# Schemtaic_Sheet_1.net
KiCad netlist of a schematic drawn in Altium Designer
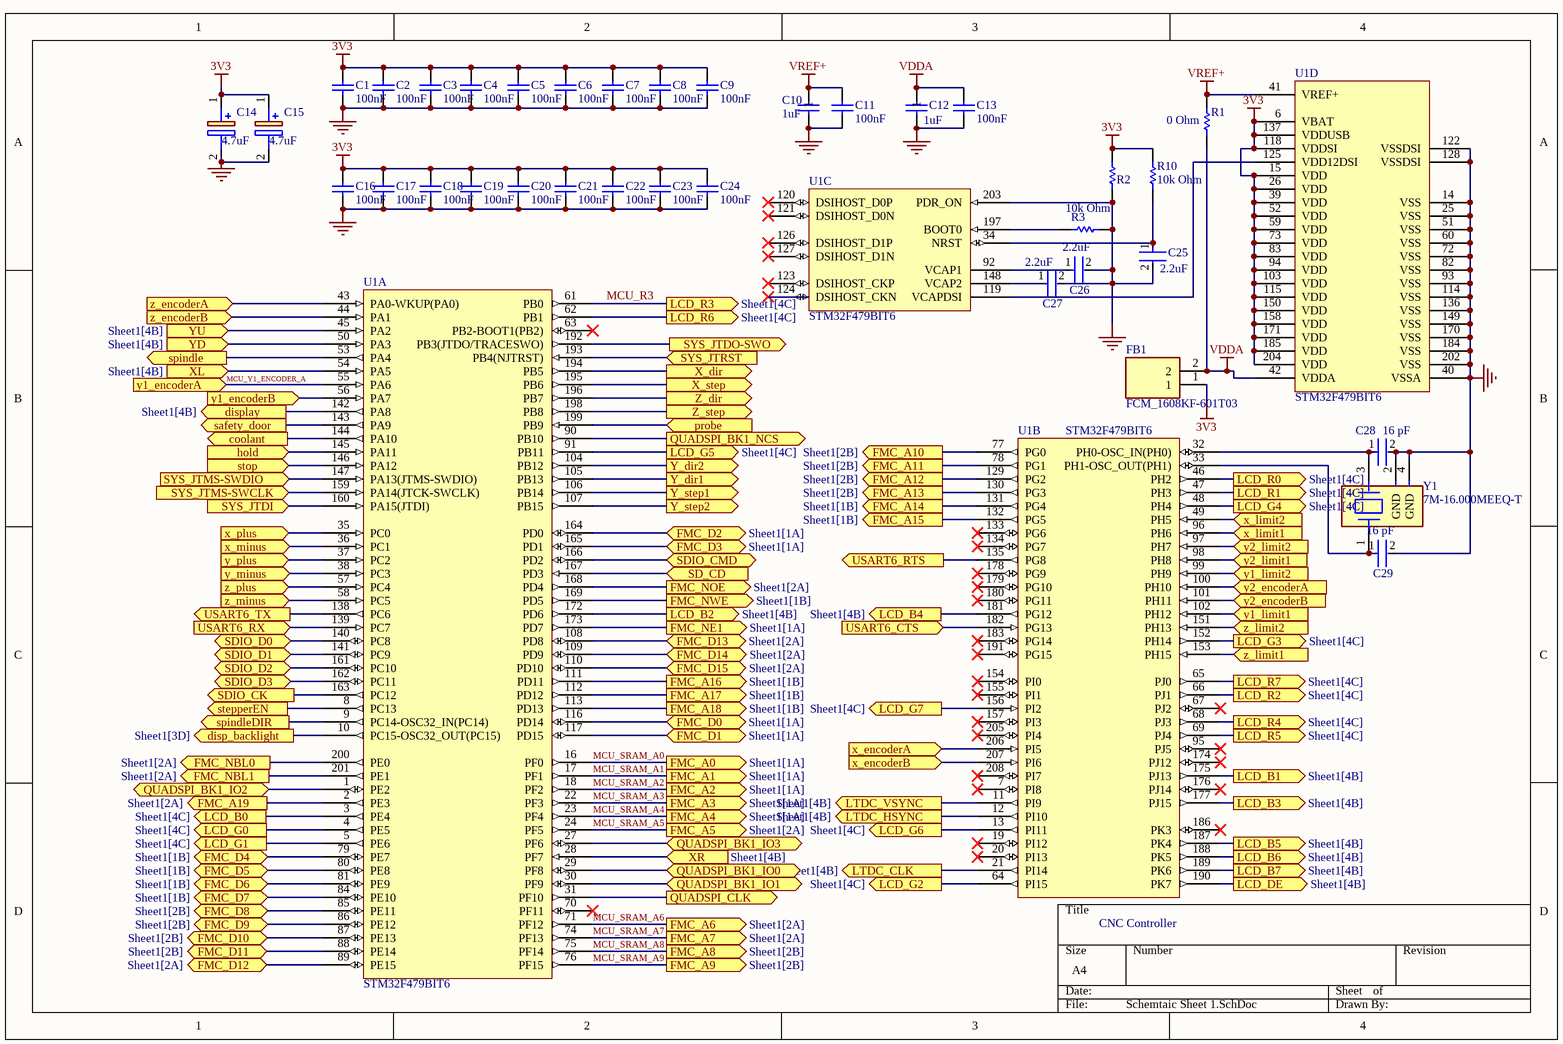
[diagram p0: Schemtaic Sheet 1.SchDoc]

(export (version "E")
  (design (tool "Eeschema 10.0.6"))
  (components
    (comp (ref "C1")
      (value "CL05B104KO5NNNC")
      (footprint "CAPC1050X55X23ML05T13")
      (description "Chip Capacitor, 100 nF, +/- 10%, 16 V, -55 to 125 degC, 0402 (1005 Metric), RoHS, Tape and Reel")
      (fields (field (name "MANUFACTURER") "Samsung Electro-Mechanics") (field (name "CAPACITANCE") "100nF"))
      (libsource (lib "Altium Content Vault") (part "CAP-NP-2"))
    )
    (comp (ref "C2")
      (value "CL05B104KO5NNNC")
      (footprint "CAPC1050X55X23ML05T13")
      (description "Chip Capacitor, 100 nF, +/- 10%, 16 V, -55 to 125 degC, 0402 (1005 Metric), RoHS, Tape and Reel")
      (fields (field (name "MANUFACTURER") "Samsung Electro-Mechanics") (field (name "CAPACITANCE") "100nF"))
      (libsource (lib "Altium Content Vault") (part "CAP-NP-2"))
    )
    (comp (ref "C3")
      (value "CL05B104KO5NNNC")
      (footprint "CAPC1050X55X23ML05T13")
      (description "Chip Capacitor, 100 nF, +/- 10%, 16 V, -55 to 125 degC, 0402 (1005 Metric), RoHS, Tape and Reel")
      (fields (field (name "MANUFACTURER") "Samsung Electro-Mechanics") (field (name "CAPACITANCE") "100nF"))
      (libsource (lib "Altium Content Vault") (part "CAP-NP-2"))
    )
    (comp (ref "C4")
      (value "CL05B104KO5NNNC")
      (footprint "CAPC1050X55X23ML05T13")
      (description "Chip Capacitor, 100 nF, +/- 10%, 16 V, -55 to 125 degC, 0402 (1005 Metric), RoHS, Tape and Reel")
      (fields (field (name "MANUFACTURER") "Samsung Electro-Mechanics") (field (name "CAPACITANCE") "100nF"))
      (libsource (lib "Altium Content Vault") (part "CAP-NP-2"))
    )
    (comp (ref "C5")
      (value "CL05B104KO5NNNC")
      (footprint "CAPC1050X55X23ML05T13")
      (description "Chip Capacitor, 100 nF, +/- 10%, 16 V, -55 to 125 degC, 0402 (1005 Metric), RoHS, Tape and Reel")
      (fields (field (name "MANUFACTURER") "Samsung Electro-Mechanics") (field (name "CAPACITANCE") "100nF"))
      (libsource (lib "Altium Content Vault") (part "CAP-NP-2"))
    )
    (comp (ref "C6")
      (value "CL05B104KO5NNNC")
      (footprint "CAPC1050X55X23ML05T13")
      (description "Chip Capacitor, 100 nF, +/- 10%, 16 V, -55 to 125 degC, 0402 (1005 Metric), RoHS, Tape and Reel")
      (fields (field (name "MANUFACTURER") "Samsung Electro-Mechanics") (field (name "CAPACITANCE") "100nF"))
      (libsource (lib "Altium Content Vault") (part "CAP-NP-2"))
    )
    (comp (ref "C7")
      (value "CL05B104KO5NNNC")
      (footprint "CAPC1050X55X23ML05T13")
      (description "Chip Capacitor, 100 nF, +/- 10%, 16 V, -55 to 125 degC, 0402 (1005 Metric), RoHS, Tape and Reel")
      (fields (field (name "MANUFACTURER") "Samsung Electro-Mechanics") (field (name "CAPACITANCE") "100nF"))
      (libsource (lib "Altium Content Vault") (part "CAP-NP-2"))
    )
    (comp (ref "C8")
      (value "CL05B104KO5NNNC")
      (footprint "CAPC1050X55X23ML05T13")
      (description "Chip Capacitor, 100 nF, +/- 10%, 16 V, -55 to 125 degC, 0402 (1005 Metric), RoHS, Tape and Reel")
      (fields (field (name "MANUFACTURER") "Samsung Electro-Mechanics") (field (name "CAPACITANCE") "100nF"))
      (libsource (lib "Altium Content Vault") (part "CAP-NP-2"))
    )
    (comp (ref "C9")
      (value "CL05B104KO5NNNC")
      (footprint "CAPC1050X55X23ML05T13")
      (description "Chip Capacitor, 100 nF, +/- 10%, 16 V, -55 to 125 degC, 0402 (1005 Metric), RoHS, Tape and Reel")
      (fields (field (name "MANUFACTURER") "Samsung Electro-Mechanics") (field (name "CAPACITANCE") "100nF"))
      (libsource (lib "Altium Content Vault") (part "CAP-NP-2"))
    )
    (comp (ref "C10")
      (value "TACL105K016XTA")
      (footprint "CAPC1609X100X15LL20")
      (fields (field (name "MANUFACTURER") "AVX Interconnect / Elco") (field (name "CAPACITANCE") "1uF"))
      (libsource (lib "Altium Content Vault") (part "CAP"))
    )
    (comp (ref "C11")
      (value "CL05B104KO5NNNC")
      (footprint "CAPC1050X55X23ML05T13")
      (description "Chip Capacitor, 100 nF, +/- 10%, 16 V, -55 to 125 degC, 0402 (1005 Metric), RoHS, Tape and Reel")
      (fields (field (name "MANUFACTURER") "Samsung Electro-Mechanics") (field (name "CAPACITANCE") "100nF"))
      (libsource (lib "Altium Content Vault") (part "CAP-NP-2"))
    )
    (comp (ref "C12")
      (value "TACL105K016XTA")
      (footprint "CAPC1609X100X15LL20")
      (fields (field (name "MANUFACTURER") "AVX Interconnect / Elco") (field (name "CAPACITANCE") "1uF"))
      (libsource (lib "Altium Content Vault") (part "CAP"))
    )
    (comp (ref "C13")
      (value "CL05B104KO5NNNC")
      (footprint "CAPC1050X55X23ML05T13")
      (description "Chip Capacitor, 100 nF, +/- 10%, 16 V, -55 to 125 degC, 0402 (1005 Metric), RoHS, Tape and Reel")
      (fields (field (name "MANUFACTURER") "Samsung Electro-Mechanics") (field (name "CAPACITANCE") "100nF"))
      (libsource (lib "Altium Content Vault") (part "CAP-NP-2"))
    )
    (comp (ref "C14")
      (value "F981C475MMAAJ6")
      (footprint "SamacSys:CAPPM169X100N")
      (description "Capacitor Polarised")
      (fields (field (name "MOUSER PART NUMBER") "581-F981C475MMAAJ6") (field (name "CAPACITANCE") "4.7uF"))
      (libsource (lib "*") (part "F981C475MMAAJ6"))
    )
    (comp (ref "C15")
      (value "F981C475MMAAJ6")
      (footprint "SamacSys:CAPPM169X100N")
      (description "Capacitor Polarised")
      (fields (field (name "MOUSER PART NUMBER") "581-F981C475MMAAJ6") (field (name "CAPACITANCE") "4.7uF"))
      (libsource (lib "*") (part "F981C475MMAAJ6"))
    )
    (comp (ref "C16")
      (value "CL05B104KO5NNNC")
      (footprint "CAPC1050X55X23ML05T13")
      (description "Chip Capacitor, 100 nF, +/- 10%, 16 V, -55 to 125 degC, 0402 (1005 Metric), RoHS, Tape and Reel")
      (fields (field (name "MANUFACTURER") "Samsung Electro-Mechanics") (field (name "CAPACITANCE") "100nF"))
      (libsource (lib "Altium Content Vault") (part "CAP-NP-2"))
    )
    (comp (ref "C17")
      (value "CL05B104KO5NNNC")
      (footprint "CAPC1050X55X23ML05T13")
      (description "Chip Capacitor, 100 nF, +/- 10%, 16 V, -55 to 125 degC, 0402 (1005 Metric), RoHS, Tape and Reel")
      (fields (field (name "MANUFACTURER") "Samsung Electro-Mechanics") (field (name "CAPACITANCE") "100nF"))
      (libsource (lib "Altium Content Vault") (part "CAP-NP-2"))
    )
    (comp (ref "C18")
      (value "CL05B104KO5NNNC")
      (footprint "CAPC1050X55X23ML05T13")
      (description "Chip Capacitor, 100 nF, +/- 10%, 16 V, -55 to 125 degC, 0402 (1005 Metric), RoHS, Tape and Reel")
      (fields (field (name "MANUFACTURER") "Samsung Electro-Mechanics") (field (name "CAPACITANCE") "100nF"))
      (libsource (lib "Altium Content Vault") (part "CAP-NP-2"))
    )
    (comp (ref "C19")
      (value "CL05B104KO5NNNC")
      (footprint "CAPC1050X55X23ML05T13")
      (description "Chip Capacitor, 100 nF, +/- 10%, 16 V, -55 to 125 degC, 0402 (1005 Metric), RoHS, Tape and Reel")
      (fields (field (name "MANUFACTURER") "Samsung Electro-Mechanics") (field (name "CAPACITANCE") "100nF"))
      (libsource (lib "Altium Content Vault") (part "CAP-NP-2"))
    )
    (comp (ref "C20")
      (value "CL05B104KO5NNNC")
      (footprint "CAPC1050X55X23ML05T13")
      (description "Chip Capacitor, 100 nF, +/- 10%, 16 V, -55 to 125 degC, 0402 (1005 Metric), RoHS, Tape and Reel")
      (fields (field (name "MANUFACTURER") "Samsung Electro-Mechanics") (field (name "CAPACITANCE") "100nF"))
      (libsource (lib "Altium Content Vault") (part "CAP-NP-2"))
    )
    (comp (ref "C21")
      (value "CL05B104KO5NNNC")
      (footprint "CAPC1050X55X23ML05T13")
      (description "Chip Capacitor, 100 nF, +/- 10%, 16 V, -55 to 125 degC, 0402 (1005 Metric), RoHS, Tape and Reel")
      (fields (field (name "MANUFACTURER") "Samsung Electro-Mechanics") (field (name "CAPACITANCE") "100nF"))
      (libsource (lib "Altium Content Vault") (part "CAP-NP-2"))
    )
    (comp (ref "C22")
      (value "CL05B104KO5NNNC")
      (footprint "CAPC1050X55X23ML05T13")
      (description "Chip Capacitor, 100 nF, +/- 10%, 16 V, -55 to 125 degC, 0402 (1005 Metric), RoHS, Tape and Reel")
      (fields (field (name "MANUFACTURER") "Samsung Electro-Mechanics") (field (name "CAPACITANCE") "100nF"))
      (libsource (lib "Altium Content Vault") (part "CAP-NP-2"))
    )
    (comp (ref "C23")
      (value "CL05B104KO5NNNC")
      (footprint "CAPC1050X55X23ML05T13")
      (description "Chip Capacitor, 100 nF, +/- 10%, 16 V, -55 to 125 degC, 0402 (1005 Metric), RoHS, Tape and Reel")
      (fields (field (name "MANUFACTURER") "Samsung Electro-Mechanics") (field (name "CAPACITANCE") "100nF"))
      (libsource (lib "Altium Content Vault") (part "CAP-NP-2"))
    )
    (comp (ref "C24")
      (value "CL05B104KO5NNNC")
      (footprint "CAPC1050X55X23ML05T13")
      (description "Chip Capacitor, 100 nF, +/- 10%, 16 V, -55 to 125 degC, 0402 (1005 Metric), RoHS, Tape and Reel")
      (fields (field (name "MANUFACTURER") "Samsung Electro-Mechanics") (field (name "CAPACITANCE") "100nF"))
      (libsource (lib "Altium Content Vault") (part "CAP-NP-2"))
    )
    (comp (ref "C25")
      (value "0603YC225KAT2A")
      (footprint "FP-0603-L_1_6_0_15-W_0_81-IPC_C")
      (description "General Purpose Ceramic Capacitor, 0603, 2.2uF, 10%, X7R, 15%, 16V")
      (fields (field (name "CAPACITANCE") "2.2uF") (field (name "TOLERANCE") "10%"))
      (libsource (lib "Altium Content Vault") (part "02cd4be3c70576c341d710602a673aa"))
    )
    (comp (ref "C26")
      (value "0603YC225KAT2A")
      (footprint "FP-0603-L_1_6_0_15-W_0_81-IPC_C")
      (description "General Purpose Ceramic Capacitor, 0603, 2.2uF, 10%, X7R, 15%, 16V")
      (fields (field (name "CAPACITANCE") "2.2uF") (field (name "TOLERANCE") "10%"))
      (libsource (lib "Altium Content Vault") (part "02cd4be3c70576c341d710602a673aa"))
    )
    (comp (ref "C27")
      (value "0603YC225KAT2A")
      (footprint "FP-0603-L_1_6_0_15-W_0_81-IPC_C")
      (description "General Purpose Ceramic Capacitor, 0603, 2.2uF, 10%, X7R, 15%, 16V")
      (fields (field (name "CAPACITANCE") "2.2uF") (field (name "TOLERANCE") "10%"))
      (libsource (lib "Altium Content Vault") (part "02cd4be3c70576c341d710602a673aa"))
    )
    (comp (ref "C28")
      (value "C0402C160F4HACTU")
      (footprint "FP-C0402-BB-MFG")
      (description "C0402 16 pF X8R 1.00% 16 V")
      (fields
        (field (name "TOLERANCE") "0.01")
        (field (name "CAPACITANCE") "16 pF")
        (field (name "OCTOPART") "https://octopart.com/c0402c160f4hactu-kemet-88724207")
      )
      (libsource (lib "Altium Content Vault") (part "b4654b650e69147ec39a6b967a45e02"))
    )
    (comp (ref "C29")
      (value "16 pF")
      (footprint "FP-C0402-BB-MFG")
      (description "C0402 16 pF X8R 1.00% 16 V")
      (fields (field (name "MANUFACTURER PART NUMBER") "C0402C160F4HACTU") (field (name "TOLERANCE") "0.01"))
      (libsource (lib "Altium Content Vault") (part "b4654b650e69147ec39a6b967a45e02"))
    )
    (comp (ref "FB1")
      (value "FCM_1608KF-601T03")
      (footprint "SamacSys:BEADC1608X95N")
      (description "Ferrite Bead")
      (fields (field (name "MANUFACTURER_PART_NUMBER") "FCM 1608KF-601T03"))
      (libsource (lib "*") (part "FCM_1608KF-601T03"))
    )
    (comp (ref "R1")
      (value "CRCW04020000Z0EDHP")
      (footprint "RESC1005X40X25ML05T10")
      (fields (field (name "MANUFACTURER") "Vishay Dale") (field (name "RESISTANCE") "0 Ohm"))
      (libsource (lib "Altium Content Vault") (part "RES"))
    )
    (comp (ref "R2")
      (value "CRCW040210K0FKEDHP")
      (footprint "RESC1005X40X25ML05T10")
      (fields (field (name "MANUFACTURER") "Vishay Dale"))
      (libsource (lib "Altium Content Vault") (part "RES"))
    )
    (comp (ref "R3")
      (value "CRCW040210K0FKEDHP")
      (footprint "RESC1005X40X25ML05T10")
      (fields (field (name "MANUFACTURER") "Vishay Dale") (field (name "RESISTANCE") "10k Ohm"))
      (libsource (lib "Altium Content Vault") (part "RES"))
    )
    (comp (ref "R10")
      (value "CRCW040210K0FKEDHP")
      (footprint "RESC1005X40X25ML05T10")
      (fields (field (name "MANUFACTURER") "Vishay Dale") (field (name "RESISTANCE") "10k Ohm"))
      (libsource (lib "Altium Content Vault") (part "RES"))
    )
    (comp (ref "U1")
      (value "STM32F479BIT6")
      (footprint "STM-LQFP208_L")
      (libsource (lib "Altium Content Vault") (part "MC-ARM-STM32F479-LQFP208"))
    )
    (comp (ref "Y1")
      (value "7M-16.000MEEQ-T")
      (footprint "FP-7M-MFG")
      (description "Crystal 16MHz, 10ppm, 10pF, 60Ω")
      (fields (field (name "TOLERANCE") "10ppm"))
      (libsource (lib "Altium Content Vault") (part "41079aabb0e87794b56622915be14ed"))
    )
  )
  (nets
    (net (code "1") (name "/FMC_A10") (class "Default")
      (node (ref "U1") (pin "77") (pinfunction "PG0_77") (pintype "bidirectional"))
    )
    (net (code "2") (name "/FMC_A11") (class "Default")
      (node (ref "U1") (pin "78") (pinfunction "PG1_78") (pintype "bidirectional"))
    )
    (net (code "3") (name "/FMC_A12") (class "Default")
      (node (ref "U1") (pin "129") (pinfunction "PG2_129") (pintype "bidirectional"))
    )
    (net (code "4") (name "/FMC_A13") (class "Default")
      (node (ref "U1") (pin "130") (pinfunction "PG3_130") (pintype "bidirectional"))
    )
    (net (code "5") (name "/FMC_A14") (class "Default")
      (node (ref "U1") (pin "131") (pinfunction "PG4_131") (pintype "bidirectional"))
    )
    (net (code "6") (name "/FMC_A15") (class "Default")
      (node (ref "U1") (pin "132") (pinfunction "PG5_132") (pintype "bidirectional"))
    )
    (net (code "7") (name "/FMC_A16") (class "Default")
      (node (ref "U1") (pin "111") (pinfunction "PD11_111") (pintype "bidirectional"))
    )
    (net (code "8") (name "/FMC_A17") (class "Default")
      (node (ref "U1") (pin "112") (pinfunction "PD12_112") (pintype "bidirectional"))
    )
    (net (code "9") (name "/FMC_A18") (class "Default")
      (node (ref "U1") (pin "113") (pinfunction "PD13_113") (pintype "bidirectional"))
    )
    (net (code "10") (name "/FMC_A19") (class "Default")
      (node (ref "U1") (pin "2") (pinfunction "PE3_2") (pintype "bidirectional"))
    )
    (net (code "11") (name "/FMC_D0") (class "Default")
      (node (ref "U1") (pin "116") (pinfunction "PD14_116") (pintype "bidirectional"))
    )
    (net (code "12") (name "/FMC_D1") (class "Default")
      (node (ref "U1") (pin "117") (pinfunction "PD15_117") (pintype "bidirectional"))
    )
    (net (code "13") (name "/FMC_D2") (class "Default")
      (node (ref "U1") (pin "164") (pinfunction "PD0_164") (pintype "bidirectional"))
    )
    (net (code "14") (name "/FMC_D3") (class "Default")
      (node (ref "U1") (pin "165") (pinfunction "PD1_165") (pintype "bidirectional"))
    )
    (net (code "15") (name "/FMC_D4") (class "Default")
      (node (ref "U1") (pin "79") (pinfunction "PE7_79") (pintype "bidirectional"))
    )
    (net (code "16") (name "/FMC_D5") (class "Default")
      (node (ref "U1") (pin "80") (pinfunction "PE8_80") (pintype "bidirectional"))
    )
    (net (code "17") (name "/FMC_D6") (class "Default")
      (node (ref "U1") (pin "81") (pinfunction "PE9_81") (pintype "bidirectional"))
    )
    (net (code "18") (name "/FMC_D7") (class "Default")
      (node (ref "U1") (pin "84") (pinfunction "PE10_84") (pintype "bidirectional"))
    )
    (net (code "19") (name "/FMC_D8") (class "Default")
      (node (ref "U1") (pin "85") (pinfunction "PE11_85") (pintype "bidirectional"))
    )
    (net (code "20") (name "/FMC_D9") (class "Default")
      (node (ref "U1") (pin "86") (pinfunction "PE12_86") (pintype "bidirectional"))
    )
    (net (code "21") (name "/FMC_D10") (class "Default")
      (node (ref "U1") (pin "87") (pinfunction "PE13_87") (pintype "bidirectional"))
    )
    (net (code "22") (name "/FMC_D11") (class "Default")
      (node (ref "U1") (pin "88") (pinfunction "PE14_88") (pintype "bidirectional"))
    )
    (net (code "23") (name "/FMC_D12") (class "Default")
      (node (ref "U1") (pin "89") (pinfunction "PE15_89") (pintype "bidirectional"))
    )
    (net (code "24") (name "/FMC_D13") (class "Default")
      (node (ref "U1") (pin "108") (pinfunction "PD8_108") (pintype "bidirectional"))
    )
    (net (code "25") (name "/FMC_D14") (class "Default")
      (node (ref "U1") (pin "109") (pinfunction "PD9_109") (pintype "bidirectional"))
    )
    (net (code "26") (name "/FMC_D15") (class "Default")
      (node (ref "U1") (pin "110") (pinfunction "PD10_110") (pintype "bidirectional"))
    )
    (net (code "27") (name "/FMC_NBL0") (class "Default")
      (node (ref "U1") (pin "200") (pinfunction "PE0_200") (pintype "bidirectional"))
    )
    (net (code "28") (name "/FMC_NBL1") (class "Default")
      (node (ref "U1") (pin "201") (pinfunction "PE1_201") (pintype "bidirectional"))
    )
    (net (code "29") (name "/FMC_NE1") (class "Default")
      (node (ref "U1") (pin "173") (pinfunction "PD7_173") (pintype "bidirectional"))
    )
    (net (code "30") (name "/FMC_NOE") (class "Default")
      (node (ref "U1") (pin "168") (pinfunction "PD4_168") (pintype "bidirectional"))
    )
    (net (code "31") (name "/FMC_NWE") (class "Default")
      (node (ref "U1") (pin "169") (pinfunction "PD5_169") (pintype "bidirectional"))
    )
    (net (code "32") (name "/LCD_B0") (class "Default")
      (node (ref "U1") (pin "3") (pinfunction "PE4_3") (pintype "bidirectional"))
    )
    (net (code "33") (name "/LCD_B1") (class "Default")
      (node (ref "U1") (pin "175") (pinfunction "PJ13_175") (pintype "bidirectional"))
    )
    (net (code "34") (name "/LCD_B2") (class "Default")
      (node (ref "U1") (pin "172") (pinfunction "PD6_172") (pintype "bidirectional"))
    )
    (net (code "35") (name "/LCD_B3") (class "Default")
      (node (ref "U1") (pin "177") (pinfunction "PJ15_177") (pintype "bidirectional"))
    )
    (net (code "36") (name "/LCD_B4") (class "Default")
      (node (ref "U1") (pin "181") (pinfunction "PG12_181") (pintype "bidirectional"))
    )
    (net (code "37") (name "/LCD_B5") (class "Default")
      (node (ref "U1") (pin "187") (pinfunction "PK4_187") (pintype "bidirectional"))
    )
    (net (code "38") (name "/LCD_B6") (class "Default")
      (node (ref "U1") (pin "188") (pinfunction "PK5_188") (pintype "bidirectional"))
    )
    (net (code "39") (name "/LCD_B7") (class "Default")
      (node (ref "U1") (pin "189") (pinfunction "PK6_189") (pintype "bidirectional"))
    )
    (net (code "40") (name "/LCD_DE") (class "Default")
      (node (ref "U1") (pin "190") (pinfunction "PK7_190") (pintype "bidirectional"))
    )
    (net (code "41") (name "/LCD_G0") (class "Default")
      (node (ref "U1") (pin "4") (pinfunction "PE5_4") (pintype "bidirectional"))
    )
    (net (code "42") (name "/LCD_G1") (class "Default")
      (node (ref "U1") (pin "5") (pinfunction "PE6_5") (pintype "bidirectional"))
    )
    (net (code "43") (name "/LCD_G2") (class "Default")
      (node (ref "U1") (pin "64") (pinfunction "PI15_64") (pintype "bidirectional"))
    )
    (net (code "44") (name "/LCD_G3") (class "Default")
      (node (ref "U1") (pin "152") (pinfunction "PH14_152") (pintype "bidirectional"))
    )
    (net (code "45") (name "/LCD_G4") (class "Default")
      (node (ref "U1") (pin "48") (pinfunction "PH4_48") (pintype "bidirectional"))
    )
    (net (code "46") (name "/LCD_G5") (class "Default")
      (node (ref "U1") (pin "91") (pinfunction "PB11_91") (pintype "bidirectional"))
    )
    (net (code "47") (name "/LCD_G6") (class "Default")
      (node (ref "U1") (pin "13") (pinfunction "PI11_13") (pintype "bidirectional"))
    )
    (net (code "48") (name "/LCD_G7") (class "Default")
      (node (ref "U1") (pin "156") (pinfunction "PI2_156") (pintype "bidirectional"))
    )
    (net (code "49") (name "/LCD_R0") (class "Default")
      (node (ref "U1") (pin "46") (pinfunction "PH2_46") (pintype "bidirectional"))
    )
    (net (code "50") (name "/LCD_R1") (class "Default")
      (node (ref "U1") (pin "47") (pinfunction "PH3_47") (pintype "bidirectional"))
    )
    (net (code "51") (name "/LCD_R2") (class "Default")
      (node (ref "U1") (pin "66") (pinfunction "PJ1_66") (pintype "bidirectional"))
    )
    (net (code "52") (name "/LCD_R4") (class "Default")
      (node (ref "U1") (pin "68") (pinfunction "PJ3_68") (pintype "bidirectional"))
    )
    (net (code "53") (name "/LCD_R5") (class "Default")
      (node (ref "U1") (pin "69") (pinfunction "PJ4_69") (pintype "bidirectional"))
    )
    (net (code "54") (name "/LCD_R6") (class "Default")
      (node (ref "U1") (pin "62") (pinfunction "PB1_62") (pintype "bidirectional"))
    )
    (net (code "55") (name "/LCD_R7") (class "Default")
      (node (ref "U1") (pin "65") (pinfunction "PJ0_65") (pintype "bidirectional"))
    )
    (net (code "56") (name "/LTDC_CLK") (class "Default")
      (node (ref "U1") (pin "21") (pinfunction "PI14_21") (pintype "bidirectional"))
    )
    (net (code "57") (name "/LTDC_HSYNC") (class "Default")
      (node (ref "U1") (pin "12") (pinfunction "PI10_12") (pintype "bidirectional"))
    )
    (net (code "58") (name "/LTDC_VSYNC") (class "Default")
      (node (ref "U1") (pin "11") (pinfunction "PI9_11") (pintype "bidirectional"))
    )
    (net (code "59") (name "/MCU_R3") (class "Default")
      (node (ref "U1") (pin "61") (pinfunction "PB0_61") (pintype "bidirectional"))
    )
    (net (code "60") (name "/MCU_SRAM_A0") (class "Default")
      (node (ref "U1") (pin "16") (pinfunction "PF0_16") (pintype "bidirectional"))
    )
    (net (code "61") (name "/MCU_SRAM_A1") (class "Default")
      (node (ref "U1") (pin "17") (pinfunction "PF1_17") (pintype "bidirectional"))
    )
    (net (code "62") (name "/MCU_SRAM_A2") (class "Default")
      (node (ref "U1") (pin "18") (pinfunction "PF2_18") (pintype "bidirectional"))
    )
    (net (code "63") (name "/MCU_SRAM_A3") (class "Default")
      (node (ref "U1") (pin "22") (pinfunction "PF3_22") (pintype "bidirectional"))
    )
    (net (code "64") (name "/MCU_SRAM_A4") (class "Default")
      (node (ref "U1") (pin "23") (pinfunction "PF4_23") (pintype "bidirectional"))
    )
    (net (code "65") (name "/MCU_SRAM_A5") (class "Default")
      (node (ref "U1") (pin "24") (pinfunction "PF5_24") (pintype "bidirectional"))
    )
    (net (code "66") (name "/MCU_SRAM_A6") (class "Default")
      (node (ref "U1") (pin "71") (pinfunction "PF12_71") (pintype "bidirectional"))
    )
    (net (code "67") (name "/MCU_SRAM_A7") (class "Default")
      (node (ref "U1") (pin "74") (pinfunction "PF13_74") (pintype "bidirectional"))
    )
    (net (code "68") (name "/MCU_SRAM_A8") (class "Default")
      (node (ref "U1") (pin "75") (pinfunction "PF14_75") (pintype "bidirectional"))
    )
    (net (code "69") (name "/MCU_SRAM_A9") (class "Default")
      (node (ref "U1") (pin "76") (pinfunction "PF15_76") (pintype "bidirectional"))
    )
    (net (code "70") (name "/MCU_Y1_ENCODER_A") (class "Default")
      (node (ref "U1") (pin "55") (pinfunction "PA6_55") (pintype "bidirectional"))
    )
    (net (code "71") (name "/QUADSPI_BK1_IO0") (class "Default")
      (node (ref "U1") (pin "29") (pinfunction "PF8_29") (pintype "bidirectional"))
    )
    (net (code "72") (name "/QUADSPI_BK1_IO1") (class "Default")
      (node (ref "U1") (pin "30") (pinfunction "PF9_30") (pintype "bidirectional"))
    )
    (net (code "73") (name "/QUADSPI_BK1_IO2") (class "Default")
      (node (ref "U1") (pin "1") (pinfunction "PE2_1") (pintype "bidirectional"))
    )
    (net (code "74") (name "/QUADSPI_BK1_IO3") (class "Default")
      (node (ref "U1") (pin "27") (pinfunction "PF6_27") (pintype "bidirectional"))
    )
    (net (code "75") (name "/QUADSPI_BK1_NCS") (class "Default")
      (node (ref "U1") (pin "90") (pinfunction "PB10_90") (pintype "bidirectional"))
    )
    (net (code "76") (name "/QUADSPI_CLK") (class "Default")
      (node (ref "U1") (pin "31") (pinfunction "PF10_31") (pintype "bidirectional"))
    )
    (net (code "77") (name "/SDIO_CK") (class "Default")
      (node (ref "U1") (pin "163") (pinfunction "PC12_163") (pintype "bidirectional"))
    )
    (net (code "78") (name "/SDIO_CMD") (class "Default")
      (node (ref "U1") (pin "166") (pinfunction "PD2_166") (pintype "bidirectional"))
    )
    (net (code "79") (name "/SDIO_D0") (class "Default")
      (node (ref "U1") (pin "140") (pinfunction "PC8_140") (pintype "bidirectional"))
    )
    (net (code "80") (name "/SDIO_D1") (class "Default")
      (node (ref "U1") (pin "141") (pinfunction "PC9_141") (pintype "bidirectional"))
    )
    (net (code "81") (name "/SDIO_D2") (class "Default")
      (node (ref "U1") (pin "161") (pinfunction "PC10_161") (pintype "bidirectional"))
    )
    (net (code "82") (name "/SDIO_D3") (class "Default")
      (node (ref "U1") (pin "162") (pinfunction "PC11_162") (pintype "bidirectional"))
    )
    (net (code "83") (name "/SD_CD") (class "Default")
      (node (ref "U1") (pin "167") (pinfunction "PD3_167") (pintype "bidirectional"))
    )
    (net (code "84") (name "/SYS_JTDI") (class "Default")
      (node (ref "U1") (pin "160") (pinfunction "PA15(JTDI)_160") (pintype "bidirectional"))
    )
    (net (code "85") (name "/SYS_JTDO-SWO") (class "Default")
      (node (ref "U1") (pin "192") (pinfunction "PB3(JTDO/TRACESWO)_192") (pintype "bidirectional"))
    )
    (net (code "86") (name "/SYS_JTMS-SWCLK") (class "Default")
      (node (ref "U1") (pin "159") (pinfunction "PA14(JTCK-SWCLK)_159") (pintype "bidirectional"))
    )
    (net (code "87") (name "/SYS_JTMS-SWDIO") (class "Default")
      (node (ref "U1") (pin "147") (pinfunction "PA13(JTMS-SWDIO)_147") (pintype "bidirectional"))
    )
    (net (code "88") (name "/SYS_JTRST") (class "Default")
      (node (ref "U1") (pin "193") (pinfunction "PB4(NJTRST)_193") (pintype "bidirectional"))
    )
    (net (code "89") (name "/USART6_CTS") (class "Default")
      (node (ref "U1") (pin "182") (pinfunction "PG13_182") (pintype "bidirectional"))
    )
    (net (code "90") (name "/USART6_RTS") (class "Default")
      (node (ref "U1") (pin "135") (pinfunction "PG8_135") (pintype "bidirectional"))
    )
    (net (code "91") (name "/USART6_RX") (class "Default")
      (node (ref "U1") (pin "139") (pinfunction "PC7_139") (pintype "bidirectional"))
    )
    (net (code "92") (name "/USART6_TX") (class "Default")
      (node (ref "U1") (pin "138") (pinfunction "PC6_138") (pintype "bidirectional"))
    )
    (net (code "93") (name "/XL") (class "Default")
      (node (ref "U1") (pin "54") (pinfunction "PA5_54") (pintype "bidirectional"))
    )
    (net (code "94") (name "/XR") (class "Default")
      (node (ref "U1") (pin "28") (pinfunction "PF7_28") (pintype "bidirectional"))
    )
    (net (code "95") (name "/X_dir") (class "Default")
      (node (ref "U1") (pin "194") (pinfunction "PB5_194") (pintype "bidirectional"))
    )
    (net (code "96") (name "/X_step") (class "Default")
      (node (ref "U1") (pin "195") (pinfunction "PB6_195") (pintype "bidirectional"))
    )
    (net (code "97") (name "/YD") (class "Default")
      (node (ref "U1") (pin "50") (pinfunction "PA3_50") (pintype "bidirectional"))
    )
    (net (code "98") (name "/YU") (class "Default")
      (node (ref "U1") (pin "45") (pinfunction "PA2_45") (pintype "bidirectional"))
    )
    (net (code "99") (name "/Y_dir1") (class "Default")
      (node (ref "U1") (pin "105") (pinfunction "PB13_105") (pintype "bidirectional"))
    )
    (net (code "100") (name "/Y_dir2") (class "Default")
      (node (ref "U1") (pin "104") (pinfunction "PB12_104") (pintype "bidirectional"))
    )
    (net (code "101") (name "/Y_step1") (class "Default")
      (node (ref "U1") (pin "106") (pinfunction "PB14_106") (pintype "bidirectional"))
    )
    (net (code "102") (name "/Y_step2") (class "Default")
      (node (ref "U1") (pin "107") (pinfunction "PB15_107") (pintype "bidirectional"))
    )
    (net (code "103") (name "/Z_dir") (class "Default")
      (node (ref "U1") (pin "196") (pinfunction "PB7_196") (pintype "bidirectional"))
    )
    (net (code "104") (name "/Z_step") (class "Default")
      (node (ref "U1") (pin "198") (pinfunction "PB8_198") (pintype "bidirectional"))
    )
    (net (code "105") (name "/coolant") (class "Default")
      (node (ref "U1") (pin "144") (pinfunction "PA10_144") (pintype "bidirectional"))
    )
    (net (code "106") (name "/disp_backlight") (class "Default")
      (node (ref "U1") (pin "10") (pinfunction "PC15-OSC32_OUT(PC15)_10") (pintype "bidirectional"))
    )
    (net (code "107") (name "/display") (class "Default")
      (node (ref "U1") (pin "142") (pinfunction "PA8_142") (pintype "bidirectional"))
    )
    (net (code "108") (name "/hold") (class "Default")
      (node (ref "U1") (pin "145") (pinfunction "PA11_145") (pintype "bidirectional"))
    )
    (net (code "109") (name "/probe") (class "Default")
      (node (ref "U1") (pin "199") (pinfunction "PB9_199") (pintype "bidirectional"))
    )
    (net (code "110") (name "/safety_door") (class "Default")
      (node (ref "U1") (pin "143") (pinfunction "PA9_143") (pintype "bidirectional"))
    )
    (net (code "111") (name "/spindle") (class "Default")
      (node (ref "U1") (pin "53") (pinfunction "PA4_53") (pintype "bidirectional"))
    )
    (net (code "112") (name "/spindleDIR") (class "Default")
      (node (ref "U1") (pin "9") (pinfunction "PC14-OSC32_IN(PC14)_9") (pintype "bidirectional"))
    )
    (net (code "113") (name "/stepperEN") (class "Default")
      (node (ref "U1") (pin "8") (pinfunction "PC13_8") (pintype "bidirectional"))
    )
    (net (code "114") (name "/stop") (class "Default")
      (node (ref "U1") (pin "146") (pinfunction "PA12_146") (pintype "bidirectional"))
    )
    (net (code "115") (name "/x_encoderA") (class "Default")
      (node (ref "U1") (pin "206") (pinfunction "PI5_206") (pintype "bidirectional"))
    )
    (net (code "116") (name "/x_encoderB") (class "Default")
      (node (ref "U1") (pin "207") (pinfunction "PI6_207") (pintype "bidirectional"))
    )
    (net (code "117") (name "/x_limit1") (class "Default")
      (node (ref "U1") (pin "96") (pinfunction "PH6_96") (pintype "bidirectional"))
    )
    (net (code "118") (name "/x_limit2") (class "Default")
      (node (ref "U1") (pin "49") (pinfunction "PH5_49") (pintype "bidirectional"))
    )
    (net (code "119") (name "/x_minus") (class "Default")
      (node (ref "U1") (pin "36") (pinfunction "PC1_36") (pintype "bidirectional"))
    )
    (net (code "120") (name "/x_plus") (class "Default")
      (node (ref "U1") (pin "35") (pinfunction "PC0_35") (pintype "bidirectional"))
    )
    (net (code "121") (name "/y1_encoderB") (class "Default")
      (node (ref "U1") (pin "56") (pinfunction "PA7_56") (pintype "bidirectional"))
    )
    (net (code "122") (name "/y1_limit1") (class "Default")
      (node (ref "U1") (pin "102") (pinfunction "PH12_102") (pintype "bidirectional"))
    )
    (net (code "123") (name "/y1_limit2") (class "Default")
      (node (ref "U1") (pin "99") (pinfunction "PH9_99") (pintype "bidirectional"))
    )
    (net (code "124") (name "/y2_encoderA") (class "Default")
      (node (ref "U1") (pin "100") (pinfunction "PH10_100") (pintype "bidirectional"))
    )
    (net (code "125") (name "/y2_encoderB") (class "Default")
      (node (ref "U1") (pin "101") (pinfunction "PH11_101") (pintype "bidirectional"))
    )
    (net (code "126") (name "/y2_limit1") (class "Default")
      (node (ref "U1") (pin "98") (pinfunction "PH8_98") (pintype "bidirectional"))
    )
    (net (code "127") (name "/y2_limit2") (class "Default")
      (node (ref "U1") (pin "97") (pinfunction "PH7_97") (pintype "bidirectional"))
    )
    (net (code "128") (name "/y_minus") (class "Default")
      (node (ref "U1") (pin "38") (pinfunction "PC3_38") (pintype "bidirectional"))
    )
    (net (code "129") (name "/y_plus") (class "Default")
      (node (ref "U1") (pin "37") (pinfunction "PC2_37") (pintype "bidirectional"))
    )
    (net (code "130") (name "/z_encoderA") (class "Default")
      (node (ref "U1") (pin "43") (pinfunction "PA0-WKUP(PA0)_43") (pintype "bidirectional"))
    )
    (net (code "131") (name "/z_encoderB") (class "Default")
      (node (ref "U1") (pin "44") (pinfunction "PA1_44") (pintype "bidirectional"))
    )
    (net (code "132") (name "/z_limit1") (class "Default")
      (node (ref "U1") (pin "153") (pinfunction "PH15_153") (pintype "bidirectional"))
    )
    (net (code "133") (name "/z_limit2") (class "Default")
      (node (ref "U1") (pin "151") (pinfunction "PH13_151") (pintype "bidirectional"))
    )
    (net (code "134") (name "/z_minus") (class "Default")
      (node (ref "U1") (pin "58") (pinfunction "PC5_58") (pintype "bidirectional"))
    )
    (net (code "135") (name "/z_plus") (class "Default")
      (node (ref "U1") (pin "57") (pinfunction "PC4_57") (pintype "bidirectional"))
    )
    (net (code "136") (name "3V3") (class "Default")
      (node (ref "C1") (pin "2") (pinfunction "2_2") (pintype "passive"))
      (node (ref "C14") (pin "1") (pinfunction "+_1") (pintype "passive"))
      (node (ref "C15") (pin "1") (pinfunction "+_1") (pintype "passive"))
      (node (ref "C16") (pin "2") (pinfunction "2_2") (pintype "passive"))
      (node (ref "C17") (pin "2") (pinfunction "2_2") (pintype "passive"))
      (node (ref "C18") (pin "2") (pinfunction "2_2") (pintype "passive"))
      (node (ref "C19") (pin "2") (pinfunction "2_2") (pintype "passive"))
      (node (ref "C2") (pin "2") (pinfunction "2_2") (pintype "passive"))
      (node (ref "C20") (pin "2") (pinfunction "2_2") (pintype "passive"))
      (node (ref "C21") (pin "2") (pinfunction "2_2") (pintype "passive"))
      (node (ref "C22") (pin "2") (pinfunction "2_2") (pintype "passive"))
      (node (ref "C23") (pin "2") (pinfunction "2_2") (pintype "passive"))
      (node (ref "C24") (pin "2") (pinfunction "2_2") (pintype "passive"))
      (node (ref "C3") (pin "2") (pinfunction "2_2") (pintype "passive"))
      (node (ref "C4") (pin "2") (pinfunction "2_2") (pintype "passive"))
      (node (ref "C5") (pin "2") (pinfunction "2_2") (pintype "passive"))
      (node (ref "C6") (pin "2") (pinfunction "2_2") (pintype "passive"))
      (node (ref "C7") (pin "2") (pinfunction "2_2") (pintype "passive"))
      (node (ref "C8") (pin "2") (pinfunction "2_2") (pintype "passive"))
      (node (ref "C9") (pin "2") (pinfunction "2_2") (pintype "passive"))
      (node (ref "FB1") (pin "1") (pinfunction "1_1") (pintype "passive"))
      (node (ref "R10") (pin "2") (pinfunction "2_2") (pintype "passive"))
      (node (ref "R2") (pin "2") (pinfunction "2_2") (pintype "passive"))
      (node (ref "U1") (pin "103") (pinfunction "VDD_103") (pintype "power_in"))
      (node (ref "U1") (pin "115") (pinfunction "VDD_115") (pintype "power_in"))
      (node (ref "U1") (pin "118") (pinfunction "VDDSI_118") (pintype "power_in"))
      (node (ref "U1") (pin "137") (pinfunction "VDDUSB_137") (pintype "power_in"))
      (node (ref "U1") (pin "15") (pinfunction "VDD_15") (pintype "power_in"))
      (node (ref "U1") (pin "150") (pinfunction "VDD_150") (pintype "power_in"))
      (node (ref "U1") (pin "158") (pinfunction "VDD_158") (pintype "power_in"))
      (node (ref "U1") (pin "171") (pinfunction "VDD_171") (pintype "power_in"))
      (node (ref "U1") (pin "185") (pinfunction "VDD_185") (pintype "power_in"))
      (node (ref "U1") (pin "204") (pinfunction "VDD_204") (pintype "power_in"))
      (node (ref "U1") (pin "26") (pinfunction "VDD_26") (pintype "power_in"))
      (node (ref "U1") (pin "39") (pinfunction "VDD_39") (pintype "power_in"))
      (node (ref "U1") (pin "52") (pinfunction "VDD_52") (pintype "power_in"))
      (node (ref "U1") (pin "59") (pinfunction "VDD_59") (pintype "power_in"))
      (node (ref "U1") (pin "6") (pinfunction "VBAT_6") (pintype "power_in"))
      (node (ref "U1") (pin "73") (pinfunction "VDD_73") (pintype "power_in"))
      (node (ref "U1") (pin "83") (pinfunction "VDD_83") (pintype "power_in"))
      (node (ref "U1") (pin "94") (pinfunction "VDD_94") (pintype "power_in"))
    )
    (net (code "137") (name "GND") (class "Default")
      (node (ref "C1") (pin "1") (pinfunction "1_1") (pintype "passive"))
      (node (ref "C10") (pin "1") (pinfunction "1_1") (pintype "passive"))
      (node (ref "C11") (pin "1") (pinfunction "1_1") (pintype "passive"))
      (node (ref "C12") (pin "1") (pinfunction "1_1") (pintype "passive"))
      (node (ref "C13") (pin "1") (pinfunction "1_1") (pintype "passive"))
      (node (ref "C14") (pin "2") (pinfunction "-_2") (pintype "passive"))
      (node (ref "C15") (pin "2") (pinfunction "-_2") (pintype "passive"))
      (node (ref "C16") (pin "1") (pinfunction "1_1") (pintype "passive"))
      (node (ref "C17") (pin "1") (pinfunction "1_1") (pintype "passive"))
      (node (ref "C18") (pin "1") (pinfunction "1_1") (pintype "passive"))
      (node (ref "C19") (pin "1") (pinfunction "1_1") (pintype "passive"))
      (node (ref "C2") (pin "1") (pinfunction "1_1") (pintype "passive"))
      (node (ref "C20") (pin "1") (pinfunction "1_1") (pintype "passive"))
      (node (ref "C21") (pin "1") (pinfunction "1_1") (pintype "passive"))
      (node (ref "C22") (pin "1") (pinfunction "1_1") (pintype "passive"))
      (node (ref "C23") (pin "1") (pinfunction "1_1") (pintype "passive"))
      (node (ref "C24") (pin "1") (pinfunction "1_1") (pintype "passive"))
      (node (ref "C25") (pin "2") (pinfunction "2_2") (pintype "passive"))
      (node (ref "C26") (pin "2") (pinfunction "2_2") (pintype "passive"))
      (node (ref "C27") (pin "2") (pinfunction "2_2") (pintype "passive"))
      (node (ref "C28") (pin "2") (pinfunction "2_2") (pintype "passive"))
      (node (ref "C29") (pin "2") (pinfunction "2_2") (pintype "passive"))
      (node (ref "C3") (pin "1") (pinfunction "1_1") (pintype "passive"))
      (node (ref "C4") (pin "1") (pinfunction "1_1") (pintype "passive"))
      (node (ref "C5") (pin "1") (pinfunction "1_1") (pintype "passive"))
      (node (ref "C6") (pin "1") (pinfunction "1_1") (pintype "passive"))
      (node (ref "C7") (pin "1") (pinfunction "1_1") (pintype "passive"))
      (node (ref "C8") (pin "1") (pinfunction "1_1") (pintype "passive"))
      (node (ref "C9") (pin "1") (pinfunction "1_1") (pintype "passive"))
      (node (ref "R2") (pin "1") (pinfunction "1_1") (pintype "passive"))
      (node (ref "R3") (pin "2") (pinfunction "2_2") (pintype "passive"))
      (node (ref "U1") (pin "114") (pinfunction "VSS_114") (pintype "power_in"))
      (node (ref "U1") (pin "122") (pinfunction "VSSDSI_122") (pintype "power_in"))
      (node (ref "U1") (pin "128") (pinfunction "VSSDSI_128") (pintype "power_in"))
      (node (ref "U1") (pin "136") (pinfunction "VSS_136") (pintype "power_in"))
      (node (ref "U1") (pin "14") (pinfunction "VSS_14") (pintype "power_in"))
      (node (ref "U1") (pin "149") (pinfunction "VSS_149") (pintype "power_in"))
      (node (ref "U1") (pin "170") (pinfunction "VSS_170") (pintype "power_in"))
      (node (ref "U1") (pin "184") (pinfunction "VSS_184") (pintype "power_in"))
      (node (ref "U1") (pin "202") (pinfunction "VSS_202") (pintype "power_in"))
      (node (ref "U1") (pin "203") (pinfunction "PDR_ON_203") (pintype "input"))
      (node (ref "U1") (pin "25") (pinfunction "VSS_25") (pintype "power_in"))
      (node (ref "U1") (pin "40") (pinfunction "VSSA_40") (pintype "power_in"))
      (node (ref "U1") (pin "51") (pinfunction "VSS_51") (pintype "power_in"))
      (node (ref "U1") (pin "60") (pinfunction "VSS_60") (pintype "power_in"))
      (node (ref "U1") (pin "72") (pinfunction "VSS_72") (pintype "power_in"))
      (node (ref "U1") (pin "82") (pinfunction "VSS_82") (pintype "power_in"))
      (node (ref "U1") (pin "93") (pinfunction "VSS_93") (pintype "power_in"))
      (node (ref "Y1") (pin "2") (pinfunction "GND_2") (pintype "power_in"))
      (node (ref "Y1") (pin "4") (pinfunction "GND_4") (pintype "power_in"))
    )
    (net (code "138") (name "Net-(U1B-PH0-OSC_IN(PH0))") (class "Default")
      (node (ref "C28") (pin "1") (pinfunction "1_1") (pintype "passive"))
      (node (ref "U1") (pin "32") (pinfunction "PH0-OSC_IN(PH0)_32") (pintype "bidirectional"))
      (node (ref "Y1") (pin "3") (pinfunction "3_3") (pintype "passive"))
    )
    (net (code "139") (name "Net-(U1B-PH1-OSC_OUT(PH1))") (class "Default")
      (node (ref "C29") (pin "1") (pinfunction "1_1") (pintype "passive"))
      (node (ref "U1") (pin "33") (pinfunction "PH1-OSC_OUT(PH1)_33") (pintype "bidirectional"))
      (node (ref "Y1") (pin "1") (pinfunction "1_1") (pintype "passive"))
    )
    (net (code "140") (name "Net-(U1C-BOOT0)") (class "Default")
      (node (ref "R3") (pin "1") (pinfunction "1_1") (pintype "passive"))
      (node (ref "U1") (pin "197") (pinfunction "BOOT0_197") (pintype "input"))
    )
    (net (code "141") (name "Net-(U1C-NRST)") (class "Default")
      (node (ref "C25") (pin "1") (pinfunction "1_1") (pintype "passive"))
      (node (ref "R10") (pin "1") (pinfunction "1_1") (pintype "passive"))
      (node (ref "U1") (pin "34") (pinfunction "NRST_34") (pintype "bidirectional"))
    )
    (net (code "142") (name "Net-(U1C-VCAP1)") (class "Default")
      (node (ref "C26") (pin "1") (pinfunction "1_1") (pintype "passive"))
      (node (ref "U1") (pin "92") (pinfunction "VCAP1_92") (pintype "passive"))
    )
    (net (code "143") (name "Net-(U1C-VCAP2)") (class "Default")
      (node (ref "C27") (pin "1") (pinfunction "1_1") (pintype "passive"))
      (node (ref "U1") (pin "148") (pinfunction "VCAP2_148") (pintype "passive"))
    )
    (net (code "144") (name "Net-(U1C-VCAPDSI)") (class "Default")
      (node (ref "U1") (pin "119") (pinfunction "VCAPDSI_119") (pintype "passive"))
      (node (ref "U1") (pin "125") (pinfunction "VDD12DSI_125") (pintype "power_in"))
    )
    (net (code "145") (name "VDDA") (class "Default")
      (node (ref "C12") (pin "2") (pinfunction "2_2") (pintype "passive"))
      (node (ref "C13") (pin "2") (pinfunction "2_2") (pintype "passive"))
      (node (ref "FB1") (pin "2") (pinfunction "2_2") (pintype "passive"))
      (node (ref "R1") (pin "1") (pinfunction "1_1") (pintype "passive"))
      (node (ref "U1") (pin "42") (pinfunction "VDDA_42") (pintype "power_in"))
    )
    (net (code "146") (name "VREF+") (class "Default")
      (node (ref "C10") (pin "2") (pinfunction "2_2") (pintype "passive"))
      (node (ref "C11") (pin "2") (pinfunction "2_2") (pintype "passive"))
      (node (ref "R1") (pin "2") (pinfunction "2_2") (pintype "passive"))
      (node (ref "U1") (pin "41") (pinfunction "VREF+_41") (pintype "power_in"))
    )
    (net (code "147") (name "unconnected-(U1A-PB2-BOOT1(PB2)-Pad63)") (class "Default")
      (node (ref "U1") (pin "63") (pinfunction "PB2-BOOT1(PB2)_63") (pintype "bidirectional+no_connect"))
    )
    (net (code "148") (name "unconnected-(U1A-PF11-Pad70)") (class "Default")
      (node (ref "U1") (pin "70") (pinfunction "PF11_70") (pintype "bidirectional+no_connect"))
    )
    (net (code "149") (name "unconnected-(U1B-PG6-Pad133)") (class "Default")
      (node (ref "U1") (pin "133") (pinfunction "PG6_133") (pintype "bidirectional+no_connect"))
    )
    (net (code "150") (name "unconnected-(U1B-PG7-Pad134)") (class "Default")
      (node (ref "U1") (pin "134") (pinfunction "PG7_134") (pintype "bidirectional+no_connect"))
    )
    (net (code "151") (name "unconnected-(U1B-PG9-Pad178)") (class "Default")
      (node (ref "U1") (pin "178") (pinfunction "PG9_178") (pintype "bidirectional+no_connect"))
    )
    (net (code "152") (name "unconnected-(U1B-PG10-Pad179)") (class "Default")
      (node (ref "U1") (pin "179") (pinfunction "PG10_179") (pintype "bidirectional+no_connect"))
    )
    (net (code "153") (name "unconnected-(U1B-PG11-Pad180)") (class "Default")
      (node (ref "U1") (pin "180") (pinfunction "PG11_180") (pintype "bidirectional+no_connect"))
    )
    (net (code "154") (name "unconnected-(U1B-PG14-Pad183)") (class "Default")
      (node (ref "U1") (pin "183") (pinfunction "PG14_183") (pintype "bidirectional+no_connect"))
    )
    (net (code "155") (name "unconnected-(U1B-PG15-Pad191)") (class "Default")
      (node (ref "U1") (pin "191") (pinfunction "PG15_191") (pintype "bidirectional+no_connect"))
    )
    (net (code "156") (name "unconnected-(U1B-PI0-Pad154)") (class "Default")
      (node (ref "U1") (pin "154") (pinfunction "PI0_154") (pintype "bidirectional+no_connect"))
    )
    (net (code "157") (name "unconnected-(U1B-PI1-Pad155)") (class "Default")
      (node (ref "U1") (pin "155") (pinfunction "PI1_155") (pintype "bidirectional+no_connect"))
    )
    (net (code "158") (name "unconnected-(U1B-PI3-Pad157)") (class "Default")
      (node (ref "U1") (pin "157") (pinfunction "PI3_157") (pintype "bidirectional+no_connect"))
    )
    (net (code "159") (name "unconnected-(U1B-PI4-Pad205)") (class "Default")
      (node (ref "U1") (pin "205") (pinfunction "PI4_205") (pintype "bidirectional+no_connect"))
    )
    (net (code "160") (name "unconnected-(U1B-PI7-Pad208)") (class "Default")
      (node (ref "U1") (pin "208") (pinfunction "PI7_208") (pintype "bidirectional+no_connect"))
    )
    (net (code "161") (name "unconnected-(U1B-PI8-Pad7)") (class "Default")
      (node (ref "U1") (pin "7") (pinfunction "PI8_7") (pintype "bidirectional+no_connect"))
    )
    (net (code "162") (name "unconnected-(U1B-PI12-Pad19)") (class "Default")
      (node (ref "U1") (pin "19") (pinfunction "PI12_19") (pintype "bidirectional+no_connect"))
    )
    (net (code "163") (name "unconnected-(U1B-PI13-Pad20)") (class "Default")
      (node (ref "U1") (pin "20") (pinfunction "PI13_20") (pintype "bidirectional+no_connect"))
    )
    (net (code "164") (name "unconnected-(U1B-PJ2-Pad67)") (class "Default")
      (node (ref "U1") (pin "67") (pinfunction "PJ2_67") (pintype "bidirectional+no_connect"))
    )
    (net (code "165") (name "unconnected-(U1B-PJ5-Pad95)") (class "Default")
      (node (ref "U1") (pin "95") (pinfunction "PJ5_95") (pintype "bidirectional+no_connect"))
    )
    (net (code "166") (name "unconnected-(U1B-PJ12-Pad174)") (class "Default")
      (node (ref "U1") (pin "174") (pinfunction "PJ12_174") (pintype "bidirectional+no_connect"))
    )
    (net (code "167") (name "unconnected-(U1B-PJ14-Pad176)") (class "Default")
      (node (ref "U1") (pin "176") (pinfunction "PJ14_176") (pintype "bidirectional+no_connect"))
    )
    (net (code "168") (name "unconnected-(U1B-PK3-Pad186)") (class "Default")
      (node (ref "U1") (pin "186") (pinfunction "PK3_186") (pintype "bidirectional+no_connect"))
    )
    (net (code "169") (name "unconnected-(U1C-DSIHOST_CKN-Pad124)") (class "Default")
      (node (ref "U1") (pin "124") (pinfunction "DSIHOST_CKN_124") (pintype "bidirectional+no_connect"))
    )
    (net (code "170") (name "unconnected-(U1C-DSIHOST_CKP-Pad123)") (class "Default")
      (node (ref "U1") (pin "123") (pinfunction "DSIHOST_CKP_123") (pintype "bidirectional+no_connect"))
    )
    (net (code "171") (name "unconnected-(U1C-DSIHOST_D0N-Pad121)") (class "Default")
      (node (ref "U1") (pin "121") (pinfunction "DSIHOST_D0N_121") (pintype "bidirectional+no_connect"))
    )
    (net (code "172") (name "unconnected-(U1C-DSIHOST_D0P-Pad120)") (class "Default")
      (node (ref "U1") (pin "120") (pinfunction "DSIHOST_D0P_120") (pintype "bidirectional+no_connect"))
    )
    (net (code "173") (name "unconnected-(U1C-DSIHOST_D1N-Pad127)") (class "Default")
      (node (ref "U1") (pin "127") (pinfunction "DSIHOST_D1N_127") (pintype "bidirectional+no_connect"))
    )
    (net (code "174") (name "unconnected-(U1C-DSIHOST_D1P-Pad126)") (class "Default")
      (node (ref "U1") (pin "126") (pinfunction "DSIHOST_D1P_126") (pintype "bidirectional+no_connect"))
    )
  )
)
